# MOS_interface.net
KiCad netlist of a schematic drawn in Altium Designer
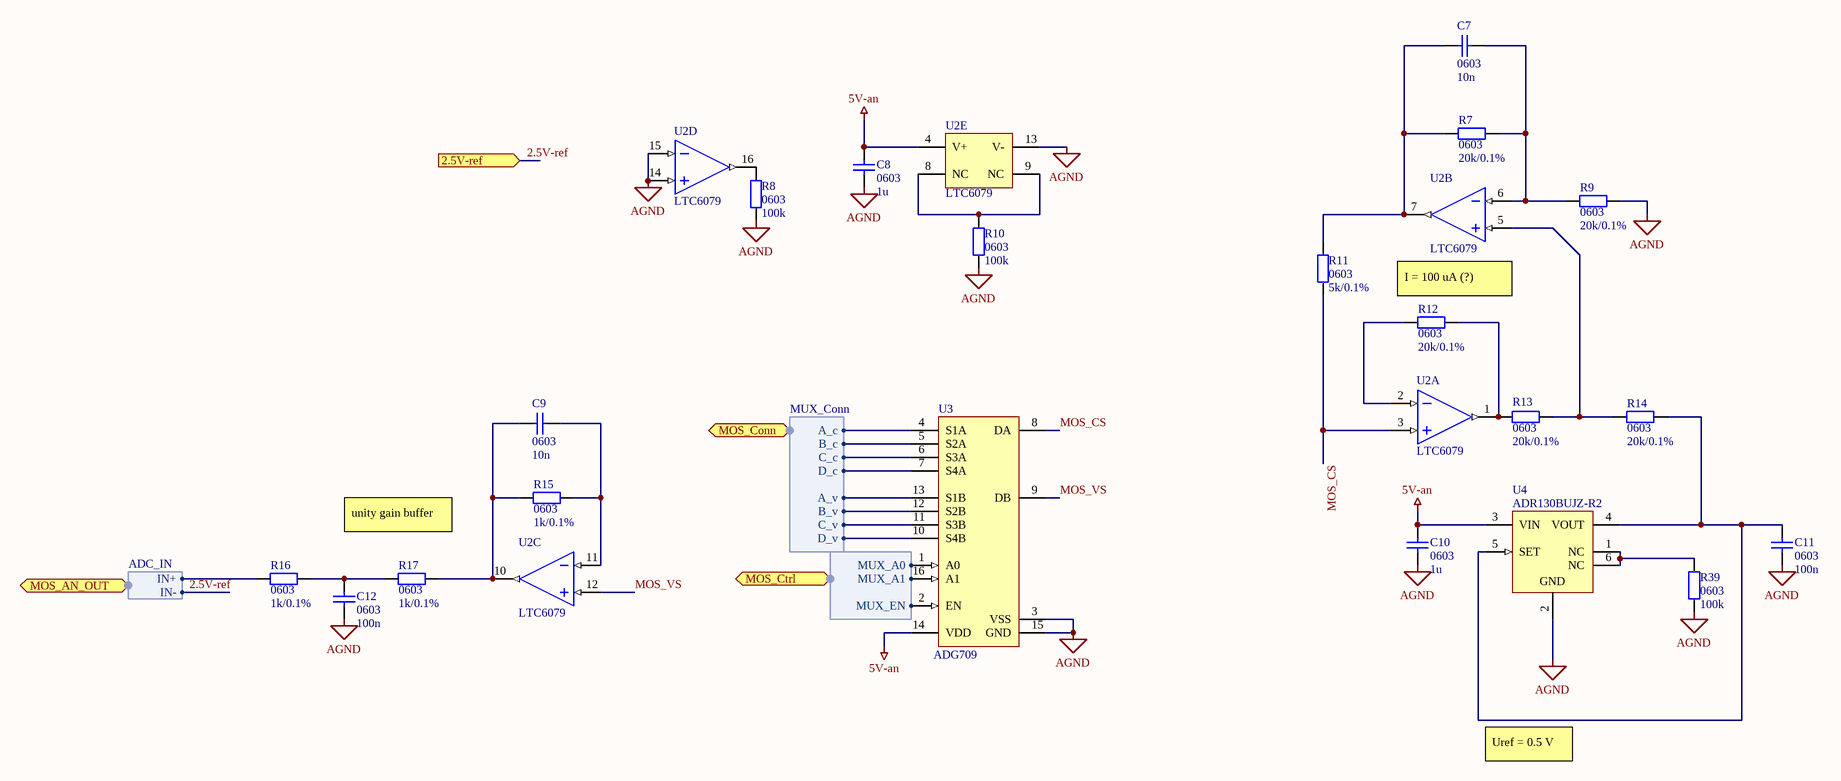
[diagram p0: MOS_interface.SchDoc]

(export (version "E")
  (design (tool "Eeschema 10.0.6"))
  (components
    (comp (ref "C7")
      (value "0603")
      (footprint "SMD_Capacitor_0603")
      (description "Capacitor")
      (fields (field (name "ALTIUM_VALUE") "10n") (field (name "PUBLISHER") "Altium Limited"))
      (libsource (lib "Miscellaneous Devices") (part "Cap"))
    )
    (comp (ref "C8")
      (value "0603")
      (footprint "SMD_Capacitor_0603")
      (description "Capacitor")
      (fields (field (name "ALTIUM_VALUE") "1u") (field (name "PUBLISHER") "Altium Limited"))
      (libsource (lib "Miscellaneous Devices") (part "Cap"))
    )
    (comp (ref "C9")
      (value "0603")
      (footprint "SMD_Capacitor_0603")
      (description "Capacitor")
      (fields (field (name "ALTIUM_VALUE") "10n") (field (name "PUBLISHER") "Altium Limited"))
      (libsource (lib "Miscellaneous Devices") (part "Cap"))
    )
    (comp (ref "C10")
      (value "0603")
      (footprint "SMD_Capacitor_0603")
      (description "Capacitor")
      (fields (field (name "ALTIUM_VALUE") "1u") (field (name "PUBLISHER") "Altium Limited"))
      (libsource (lib "Miscellaneous Devices") (part "Cap"))
    )
    (comp (ref "C11")
      (value "0603")
      (footprint "SMD_Capacitor_0603")
      (description "Capacitor")
      (fields (field (name "ALTIUM_VALUE") "100n") (field (name "PUBLISHER") "Altium Limited"))
      (libsource (lib "Miscellaneous Devices") (part "Cap"))
    )
    (comp (ref "C12")
      (value "0603")
      (footprint "SMD_Capacitor_0603")
      (description "Capacitor")
      (fields (field (name "ALTIUM_VALUE") "100n") (field (name "PUBLISHER") "Altium Limited"))
      (libsource (lib "Miscellaneous Devices") (part "Cap"))
    )
    (comp (ref "R7")
      (value "0603")
      (footprint "SMD_Resistor_0603")
      (description "Resistor")
      (fields (field (name "ALTIUM_VALUE") "20k/0.1%") (field (name "PUBLISHER") "Altium Limited"))
      (libsource (lib "Miscellaneous Devices") (part "Res2"))
    )
    (comp (ref "R8")
      (value "0603")
      (footprint "SMD_Resistor_0603")
      (description "Resistor")
      (fields (field (name "ALTIUM_VALUE") "100k") (field (name "PUBLISHER") "Altium Limited"))
      (libsource (lib "") (part "Res2_2"))
    )
    (comp (ref "R9")
      (value "0603")
      (footprint "SMD_Resistor_0603")
      (description "Resistor")
      (fields (field (name "ALTIUM_VALUE") "20k/0.1%") (field (name "PUBLISHER") "Altium Limited"))
      (libsource (lib "Miscellaneous Devices") (part "Res2"))
    )
    (comp (ref "R10")
      (value "0603")
      (footprint "SMD_Resistor_0603")
      (description "Resistor")
      (fields (field (name "ALTIUM_VALUE") "100k") (field (name "PUBLISHER") "Altium Limited"))
      (libsource (lib "") (part "Res2_2"))
    )
    (comp (ref "R11")
      (value "0603")
      (footprint "SMD_Resistor_0603")
      (description "Resistor")
      (fields (field (name "ALTIUM_VALUE") "5k/0.1%") (field (name "PUBLISHER") "Altium Limited"))
      (libsource (lib "") (part "Res2_2"))
    )
    (comp (ref "R12")
      (value "0603")
      (footprint "SMD_Resistor_0603")
      (description "Resistor")
      (fields (field (name "ALTIUM_VALUE") "20k/0.1%") (field (name "PUBLISHER") "Altium Limited"))
      (libsource (lib "Miscellaneous Devices") (part "Res2"))
    )
    (comp (ref "R13")
      (value "0603")
      (footprint "SMD_Resistor_0603")
      (description "Resistor")
      (fields (field (name "ALTIUM_VALUE") "20k/0.1%") (field (name "PUBLISHER") "Altium Limited"))
      (libsource (lib "Miscellaneous Devices") (part "Res2"))
    )
    (comp (ref "R14")
      (value "0603")
      (footprint "SMD_Resistor_0603")
      (description "Resistor")
      (fields (field (name "ALTIUM_VALUE") "20k/0.1%") (field (name "PUBLISHER") "Altium Limited"))
      (libsource (lib "Miscellaneous Devices") (part "Res2"))
    )
    (comp (ref "R15")
      (value "0603")
      (footprint "SMD_Resistor_0603")
      (description "Resistor")
      (fields (field (name "ALTIUM_VALUE") "1k/0.1%") (field (name "PUBLISHER") "Altium Limited"))
      (libsource (lib "") (part "Res2_1"))
    )
    (comp (ref "R16")
      (value "0603")
      (footprint "SMD_Resistor_0603")
      (description "Resistor")
      (fields (field (name "ALTIUM_VALUE") "1k/0.1%") (field (name "PUBLISHER") "Altium Limited"))
      (libsource (lib "") (part "Res2_1"))
    )
    (comp (ref "R17")
      (value "0603")
      (footprint "SMD_Resistor_0603")
      (description "Resistor")
      (fields (field (name "ALTIUM_VALUE") "1k/0.1%") (field (name "PUBLISHER") "Altium Limited"))
      (libsource (lib "") (part "Res2_1"))
    )
    (comp (ref "R39")
      (value "0603")
      (footprint "SMD_Resistor_0603")
      (description "Resistor")
      (fields (field (name "ALTIUM_VALUE") "100k") (field (name "PUBLISHER") "Altium Limited"))
      (libsource (lib "") (part "Res2_2"))
    )
    (comp (ref "U2")
      (value "LTC6079")
      (footprint "SSOP-16")
      (description "Rail-to-rail, quad operational amplifier. Library compatible with LTC608X LTC607X op-amps")
      (fields (field (name "MANUFACTURER") "Linear Technology"))
      (libsource (lib "") (part "LTC6079_1"))
    )
    (comp (ref "U3")
      (value "ADG709")
      (footprint "TSSOP16")
      (description "CMOS Analog 4-Channel Multiplexer")
      (fields (field (name "MANUFACTURER") "Analog Devices") (field (name "MANUFACTURERPARTNUMBER") "ADG709"))
      (libsource (lib "microcircuits_miscellaneous") (part "ADG709"))
    )
    (comp (ref "U4")
      (value "ADR130BUJZ-R2")
      (footprint "ADI-UJ-6_M")
      (fields (field (name "MANUFACTURER") "Analog Devices"))
      (libsource (lib "Analog Devices Amplifiers and Linear Voltage References") (part "ADR130BUJZ-R2"))
    )
  )
  (nets
    (net (code "5") (name "/A_c") (class "Default")
      (node (ref "U3") (pin "4") (pinfunction "S1A_4") (pintype "passive"))
    )
    (net (code "6") (name "/A_v") (class "Default")
      (node (ref "U3") (pin "13") (pinfunction "S1B_13") (pintype "passive"))
    )
    (net (code "7") (name "/B_c") (class "Default")
      (node (ref "U3") (pin "5") (pinfunction "S2A_5") (pintype "passive"))
    )
    (net (code "8") (name "/B_v") (class "Default")
      (node (ref "U3") (pin "12") (pinfunction "S2B_12") (pintype "passive"))
    )
    (net (code "9") (name "/C_c") (class "Default")
      (node (ref "U3") (pin "6") (pinfunction "S3A_6") (pintype "passive"))
    )
    (net (code "10") (name "/C_v") (class "Default")
      (node (ref "U3") (pin "11") (pinfunction "S3B_11") (pintype "passive"))
    )
    (net (code "11") (name "/D_c") (class "Default")
      (node (ref "U3") (pin "7") (pinfunction "S4A_7") (pintype "passive"))
    )
    (net (code "12") (name "/D_v") (class "Default")
      (node (ref "U3") (pin "10") (pinfunction "S4B_10") (pintype "passive"))
    )
    (net (code "13") (name "/IN+") (class "Default")
      (node (ref "R16") (pin "1") (pinfunction "1_1") (pintype "passive"))
    )
    (net (code "14") (name "/MOS_CS") (class "Default")
      (node (ref "R11") (pin "1") (pinfunction "1_1") (pintype "passive"))
      (node (ref "U2") (pin "3") (pinfunction "IN+_A_3") (pintype "input"))
      (node (ref "U3") (pin "8") (pinfunction "DA_8") (pintype "passive"))
    )
    (net (code "15") (name "/MOS_VS") (class "Default")
      (node (ref "U2") (pin "12") (pinfunction "IN+_C_12") (pintype "input"))
      (node (ref "U3") (pin "9") (pinfunction "DB_9") (pintype "passive"))
    )
    (net (code "16") (name "/MUX_A0") (class "Default")
      (node (ref "U3") (pin "1") (pinfunction "A0_1") (pintype "input"))
    )
    (net (code "17") (name "/MUX_A1") (class "Default")
      (node (ref "U3") (pin "16") (pinfunction "A1_16") (pintype "input"))
    )
    (net (code "18") (name "/MUX_EN") (class "Default")
      (node (ref "U3") (pin "2") (pinfunction "EN_2") (pintype "input"))
    )
    (net (code "22") (name "5V-an") (class "Default")
      (node (ref "C10") (pin "2") (pinfunction "2_2") (pintype "passive"))
      (node (ref "C8") (pin "2") (pinfunction "2_2") (pintype "passive"))
      (node (ref "U2") (pin "4") (pinfunction "V+_4") (pintype "power_in"))
      (node (ref "U3") (pin "14") (pinfunction "VDD_14") (pintype "power_in"))
      (node (ref "U4") (pin "3") (pinfunction "VIN_3") (pintype "power_in"))
    )
    (net (code "23") (name "AGND") (class "Default")
      (node (ref "C10") (pin "1") (pinfunction "1_1") (pintype "passive"))
      (node (ref "C11") (pin "1") (pinfunction "1_1") (pintype "passive"))
      (node (ref "C12") (pin "1") (pinfunction "1_1") (pintype "passive"))
      (node (ref "C8") (pin "1") (pinfunction "1_1") (pintype "passive"))
      (node (ref "R10") (pin "1") (pinfunction "1_1") (pintype "passive"))
      (node (ref "R39") (pin "1") (pinfunction "1_1") (pintype "passive"))
      (node (ref "R8") (pin "1") (pinfunction "1_1") (pintype "passive"))
      (node (ref "R9") (pin "1") (pinfunction "1_1") (pintype "passive"))
      (node (ref "U2") (pin "13") (pinfunction "V-_13") (pintype "power_in"))
      (node (ref "U2") (pin "14") (pinfunction "IN+_D_14") (pintype "input"))
      (node (ref "U2") (pin "15") (pinfunction "IN-_D_15") (pintype "input"))
      (node (ref "U3") (pin "15") (pinfunction "GND_15") (pintype "power_in"))
      (node (ref "U3") (pin "3") (pinfunction "VSS_3") (pintype "power_in"))
      (node (ref "U4") (pin "2") (pinfunction "GND_2") (pintype "power_in"))
    )
    (net (code "24") (name "Net-(C12-Pad2)") (class "Default")
      (node (ref "C12") (pin "2") (pinfunction "2_2") (pintype "passive"))
      (node (ref "R16") (pin "2") (pinfunction "2_2") (pintype "passive"))
      (node (ref "R17") (pin "1") (pinfunction "1_1") (pintype "passive"))
    )
    (net (code "25") (name "Net-(R10-Pad2)") (class "Default")
      (node (ref "R10") (pin "2") (pinfunction "2_2") (pintype "passive"))
      (node (ref "U2") (pin "8") (pinfunction "NC_8") (pintype "passive"))
      (node (ref "U2") (pin "9") (pinfunction "NC_9") (pintype "passive"))
    )
    (net (code "26") (name "Net-(R39-Pad2)") (class "Default")
      (node (ref "R39") (pin "2") (pinfunction "2_2") (pintype "passive"))
      (node (ref "U4") (pin "1") (pinfunction "NC_1") (pintype "passive"))
      (node (ref "U4") (pin "6") (pinfunction "NC_6") (pintype "passive"))
    )
    (net (code "27") (name "Net-(U2A-IN-_A)") (class "Default")
      (node (ref "R12") (pin "2") (pinfunction "2_2") (pintype "passive"))
      (node (ref "U2") (pin "2") (pinfunction "IN-_A_2") (pintype "input"))
    )
    (net (code "28") (name "Net-(U2A-OUT_A)") (class "Default")
      (node (ref "R12") (pin "1") (pinfunction "1_1") (pintype "passive"))
      (node (ref "R13") (pin "2") (pinfunction "2_2") (pintype "passive"))
      (node (ref "U2") (pin "1") (pinfunction "OUT_A_1") (pintype "output"))
    )
    (net (code "29") (name "Net-(U2B-IN+_B)") (class "Default")
      (node (ref "R13") (pin "1") (pinfunction "1_1") (pintype "passive"))
      (node (ref "R14") (pin "2") (pinfunction "2_2") (pintype "passive"))
      (node (ref "U2") (pin "5") (pinfunction "IN+_B_5") (pintype "input"))
    )
    (net (code "30") (name "Net-(U2B-IN-_B)") (class "Default")
      (node (ref "C7") (pin "1") (pinfunction "1_1") (pintype "passive"))
      (node (ref "R7") (pin "1") (pinfunction "1_1") (pintype "passive"))
      (node (ref "R9") (pin "2") (pinfunction "2_2") (pintype "passive"))
      (node (ref "U2") (pin "6") (pinfunction "IN-_B_6") (pintype "input"))
    )
    (net (code "31") (name "Net-(U2B-OUT_B)") (class "Default")
      (node (ref "C7") (pin "2") (pinfunction "2_2") (pintype "passive"))
      (node (ref "R11") (pin "2") (pinfunction "2_2") (pintype "passive"))
      (node (ref "R7") (pin "2") (pinfunction "2_2") (pintype "passive"))
      (node (ref "U2") (pin "7") (pinfunction "OUT_B_7") (pintype "output"))
    )
    (net (code "32") (name "Net-(U2C-IN-_C)") (class "Default")
      (node (ref "C9") (pin "1") (pinfunction "1_1") (pintype "passive"))
      (node (ref "R15") (pin "2") (pinfunction "2_2") (pintype "passive"))
      (node (ref "U2") (pin "11") (pinfunction "IN-_C_11") (pintype "input"))
    )
    (net (code "33") (name "Net-(U2C-OUT_C)") (class "Default")
      (node (ref "C9") (pin "2") (pinfunction "2_2") (pintype "passive"))
      (node (ref "R15") (pin "1") (pinfunction "1_1") (pintype "passive"))
      (node (ref "R17") (pin "2") (pinfunction "2_2") (pintype "passive"))
      (node (ref "U2") (pin "10") (pinfunction "OUT_C_10") (pintype "output"))
    )
    (net (code "34") (name "Net-(U2D-OUT_D)") (class "Default")
      (node (ref "R8") (pin "2") (pinfunction "2_2") (pintype "passive"))
      (node (ref "U2") (pin "16") (pinfunction "OUT_D_16") (pintype "output"))
    )
    (net (code "35") (name "Net-(U4-SET)") (class "Default")
      (node (ref "C11") (pin "2") (pinfunction "2_2") (pintype "passive"))
      (node (ref "R14") (pin "1") (pinfunction "1_1") (pintype "passive"))
      (node (ref "U4") (pin "4") (pinfunction "VOUT_4") (pintype "power_in"))
      (node (ref "U4") (pin "5") (pinfunction "SET_5") (pintype "input"))
    )
  )
)
